# node24-channel.net
KiCad netlist of a schematic drawn in Altium Designer
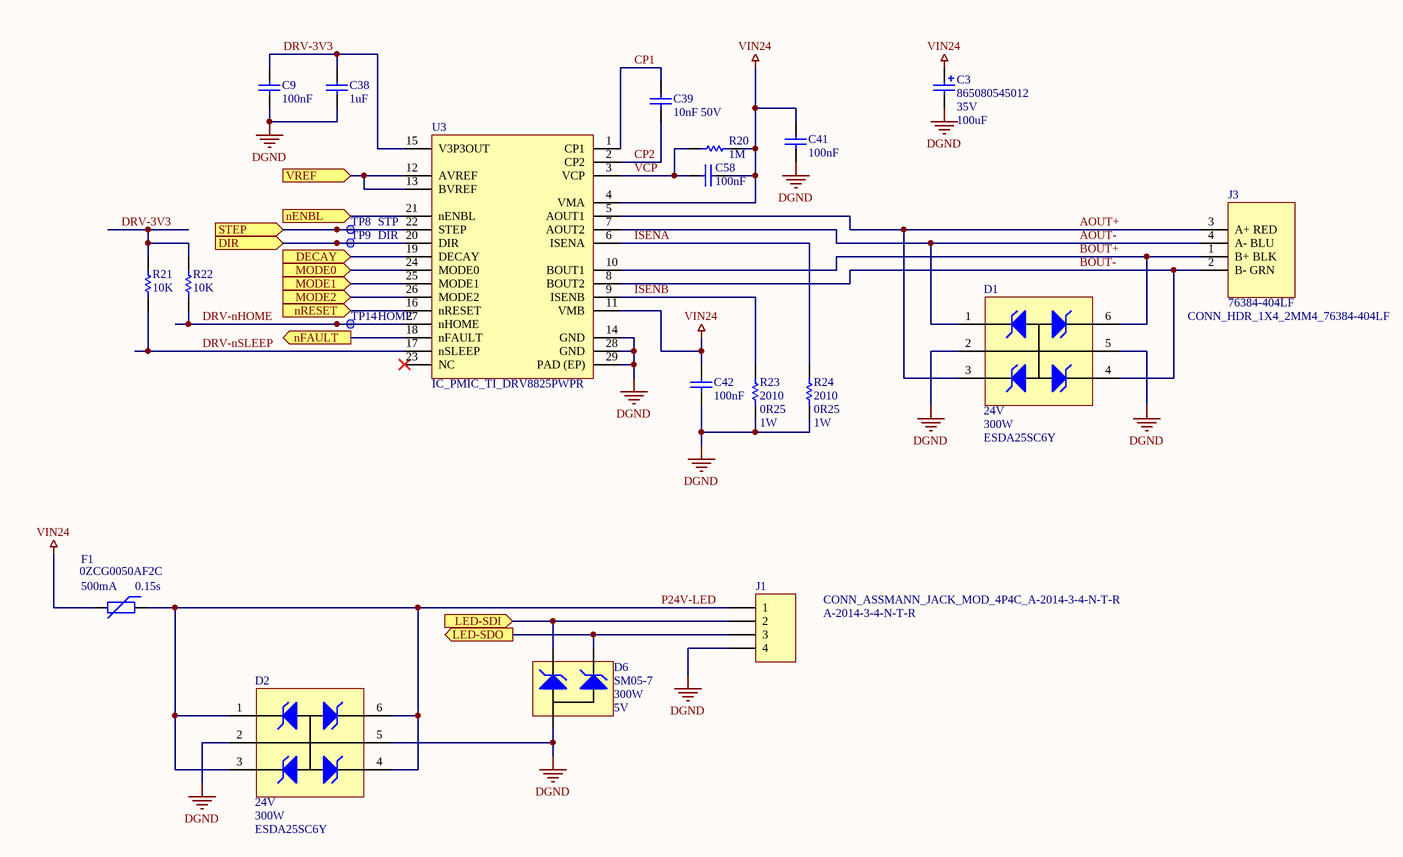
[diagram p0: node24-channel.SchDoc]

(export (version "E")
  (design (tool "Eeschema 10.0.6"))
  (components
    (comp (ref "C3")
      (value "CAP_ALUM_100UF_35V_6MM3_SMT_865080545012")
      (footprint "CAPAE_D6MM3")
      (fields
        (field (name "MANUFACTURER") "Wurth Electronics")
        (field (name "MANUFACTURER PART NUMBER") "865080545012")
        (field (name "VOLTAGE RATING (DC)") "35V")
        (field (name "CAPACITANCE") "100uF")
      )
      (libsource (lib "node") (part "CAP_ALUM_100UF_35V_6MM3_SMT_865080545012"))
    )
    (comp (ref "C9")
      (value "100nF")
      (footprint "CAPC0603(1608)100_L")
      (description "CAP 100nF 50V ±20% 0603 (1608 Metric) Thickness 1mm SMD")
      (fields (field (name "TOLERANCE") "Â±20%"))
      (libsource (lib "Altium Content Vault") (part "CAP"))
    )
    (comp (ref "C38")
      (value "1uF")
      (footprint "CAPC0603(1608)100_L")
      (description "CAP 1uF 10V ±20% 0603 (1608 Metric) Thickness 1mm SMD")
      (fields (field (name "TOLERANCE") "Â±20%"))
      (libsource (lib "Altium Content Vault") (part "CAP"))
    )
    (comp (ref "C39")
      (value "10nF 50V")
      (footprint "CAPC0603(1608)100_L")
      (description "CAP 10nF 50V ±20% 0603 (1608 Metric) Thickness 1mm SMD")
      (fields (field (name "TOLERANCE") "Â±20%"))
      (libsource (lib "Altium Content Vault") (part "CAP"))
    )
    (comp (ref "C41")
      (value "100nF")
      (footprint "CAPC0603(1608)100_L")
      (description "CAP 100nF 50V ±20% 0603 (1608 Metric) Thickness 1mm SMD")
      (fields (field (name "TOLERANCE") "Â±20%"))
      (libsource (lib "Altium Content Vault") (part "CAP"))
    )
    (comp (ref "C42")
      (value "100nF")
      (footprint "CAPC0603(1608)100_L")
      (description "CAP 100nF 50V ±20% 0603 (1608 Metric) Thickness 1mm SMD")
      (fields (field (name "TOLERANCE") "Â±20%"))
      (libsource (lib "Altium Content Vault") (part "CAP"))
    )
    (comp (ref "C58")
      (value "100nF")
      (footprint "CAPC0603(1608)100_L")
      (description "CAP 100nF 50V ±20% 0603 (1608 Metric) Thickness 1mm SMD")
      (fields (field (name "TOLERANCE") "Â±20%"))
      (libsource (lib "Altium Content Vault") (part "CAP"))
    )
    (comp (ref "D1")
      (value "TVS_24V_QUAD_300W_SOT23-6_ESDA25SC6Y")
      (footprint "SOT23-6L")
      (description "TVS DIODE 24VWM 30VC SOT23")
      (fields
        (field (name "MANUFACTURER") "STMicroelectronics")
        (field (name "OPERATING SUPPLY VOLTAGE") "24V")
        (field (name "PEAK PULSE POWER") "300W")
        (field (name "MANUFACTURER PART NUMBER") "ESDA25SC6Y")
      )
      (libsource (lib "node") (part "TVS_24V_QUAD_300W_SOT23-6_ESDA25SC6Y"))
    )
    (comp (ref "D2")
      (value "TVS_24V_QUAD_300W_SOT23-6_ESDA25SC6Y")
      (footprint "SOT23-6L")
      (description "TVS DIODE 24VWM 30VC SOT23")
      (fields
        (field (name "MANUFACTURER") "STMicroelectronics")
        (field (name "OPERATING SUPPLY VOLTAGE") "24V")
        (field (name "PEAK PULSE POWER") "300W")
        (field (name "MANUFACTURER PART NUMBER") "ESDA25SC6Y")
      )
      (libsource (lib "node") (part "TVS_24V_QUAD_300W_SOT23-6_ESDA25SC6Y"))
    )
    (comp (ref "D6")
      (value "TVS_5V_DUAL_SOT23-3_SM05-7")
      (footprint "SOT-23")
      (description "TVS DIODE 5VWM 20.6VC SOT23")
      (fields
        (field (name "MANUFACTURER") "Diodes")
        (field (name "MANUFACTURER PART NUMBER") "SM05-7")
        (field (name "MAX POWER DISSIPATION") "300W")
        (field (name "REVERSE STANDOFF VOLTAGE") "5V")
      )
      (libsource (lib "node") (part "TVS_5V_DUAL_SOT23-3_SM05-7"))
    )
    (comp (ref "F1")
      (value "FUSE_BELFUSE_PTC_30V_500MA_1812_0ZCG0050AF2C")
      (footprint "FUSE_1812")
      (description "PTC RESETTABLE 30V 500MA 1812")
      (fields
        (field (name "MANUFACTURER") "Bel")
        (field (name "HOLD CURRENT") "500mA")
        (field (name "TIME TO TRIP") "0.15s")
        (field (name "MANUFACTURER PART NUMBER") "0ZCG0050AF2C")
      )
      (libsource (lib "node") (part "FUSE_BELFUSE_PTC_30V_500MA_1812_0ZCG0050AF2C"))
    )
    (comp (ref "J1")
      (value "CONN_ASSMANN_JACK_MOD_4P4C_A-2014-3-4-N-T-R")
      (footprint "CON_JACK_MOD_4P4C_ASSMANN_A-2014-3-4-N-T-R")
      (description "CONN MOD JACK 4P4C VERT")
      (fields
        (field (name "MANUFACTURER") "Assmann")
        (field (name "MANUFACTURER PART NUMBER") "A-2014-3-4-N-T-R")
      )
      (libsource (lib "node") (part "CONN_ASSMANN_JACK_MOD_4P4C_A-2014-3-4-N-T-R"))
    )
    (comp (ref "J3")
      (value "CONN_HDR_1X4_2MM4_76384-404LF")
      (footprint "HDR_1x4_2R54_V_M")
      (fields
        (field (name "MANUFACTURER") "Amphenol FCI")
        (field (name "MANUFACTURER PART NUMBER") "76384-404LF")
      )
      (libsource (lib "node") (part "CONN_HDR_1X4_2MM4_76384-404LF"))
    )
    (comp (ref "R20")
      (value "1M")
      (footprint "RESC0603(1608)_L")
      (description "1M 0.1W 1% 0603 (1608 Metric)  SMD")
      (fields (field (name "POWER") "0.1 W") (field (name "TOLERANCE") "1 %"))
      (libsource (lib "Altium Content Vault") (part "RES"))
    )
    (comp (ref "R21")
      (value "10K")
      (footprint "RESC0603(1608)_L")
      (description "10K 0.1W 1% 0603 (1608 Metric)  SMD")
      (fields (field (name "POWER") "0.1 W") (field (name "TOLERANCE") "1 %"))
      (libsource (lib "Altium Content Vault") (part "RES"))
    )
    (comp (ref "R22")
      (value "10K")
      (footprint "RESC0603(1608)_L")
      (description "10K 0.1W 1% 0603 (1608 Metric)  SMD")
      (fields (field (name "POWER") "0.1 W") (field (name "TOLERANCE") "1 %"))
      (libsource (lib "Altium Content Vault") (part "RES"))
    )
    (comp (ref "R23")
      (value "RES_2010_0R25_1W_CSRN2010FKR250")
      (footprint "RES2010N")
      (description "Res Thick Film 2010 0.25 Ohm 1% 1W ±250ppm/C Molded SMD Plastic T/R")
      (fields
        (field (name "MANUFACTURER") "Stackpole Electronics")
        (field (name "MANUFACTURER PART NUMBER") "CSRN2010FKR250")
        (field (name "CASE CODE (IMPERIAL)") "2010")
        (field (name "RESISTANCE") "0R25")
        (field (name "POWER RATING") "1W")
      )
      (libsource (lib "node") (part "RES_2010_0R25_1W_CSRN2010FKR250"))
    )
    (comp (ref "R24")
      (value "RES_2010_0R25_1W_CSRN2010FKR250")
      (footprint "RES2010N")
      (description "Res Thick Film 2010 0.25 Ohm 1% 1W ±250ppm/C Molded SMD Plastic T/R")
      (fields
        (field (name "MANUFACTURER") "Stackpole Electronics")
        (field (name "MANUFACTURER PART NUMBER") "CSRN2010FKR250")
        (field (name "CASE CODE (IMPERIAL)") "2010")
        (field (name "RESISTANCE") "0R25")
        (field (name "POWER RATING") "1W")
      )
      (libsource (lib "node") (part "RES_2010_0R25_1W_CSRN2010FKR250"))
    )
    (comp (ref "TP8")
      (value "STP")
      (footprint "TP_1MM")
      (description "TEST_PAD_NO_PART")
      (fields (field (name "MANUFACTURER PART NUMBER") "None -- copper test pad"))
      (libsource (lib "node") (part "TEST_POINT"))
    )
    (comp (ref "TP9")
      (value "DIR")
      (footprint "TP_1MM")
      (description "TEST_PAD_NO_PART")
      (fields (field (name "MANUFACTURER PART NUMBER") "None -- copper test pad"))
      (libsource (lib "node") (part "TEST_POINT"))
    )
    (comp (ref "TP14")
      (value "HOME")
      (footprint "TP_1MM")
      (description "TEST_PAD_NO_PART")
      (fields (field (name "MANUFACTURER PART NUMBER") "None -- copper test pad"))
      (libsource (lib "node") (part "TEST_POINT"))
    )
    (comp (ref "U3")
      (value "IC_PMIC_TI_DRV8825PWPR")
      (footprint "IC_TSSOP28_0MM65_EP52X31")
      (description "IC MOTOR DRIVER PAR 28HTSSOP")
      (fields
        (field (name "MANUFACTURER") "Texas Instruments")
        (field (name "MANUFACTURER PART NUMBER") "DRV8825PWPR")
      )
      (libsource (lib "node") (part "IC_PMIC_TI_DRV8825PWPR"))
    )
  )
  (nets
    (net (code "1") (name "/AOUT+") (class "Default")
      (node (ref "D1") (pin "3") (pinfunction "K2_3") (pintype "passive"))
      (node (ref "J3") (pin "3") (pinfunction "A+_RED_3") (pintype "passive"))
      (node (ref "U3") (pin "5") (pinfunction "AOUT1_5") (pintype "passive"))
    )
    (net (code "2") (name "/AOUT-") (class "Default")
      (node (ref "D1") (pin "1") (pinfunction "K1_1") (pintype "passive"))
      (node (ref "J3") (pin "4") (pinfunction "A-_BLU_4") (pintype "passive"))
      (node (ref "U3") (pin "7") (pinfunction "AOUT2_7") (pintype "passive"))
    )
    (net (code "3") (name "/BOUT+") (class "Default")
      (node (ref "D1") (pin "6") (pinfunction "K4_6") (pintype "passive"))
      (node (ref "J3") (pin "1") (pinfunction "B+_BLK_1") (pintype "passive"))
      (node (ref "U3") (pin "10") (pinfunction "BOUT1_10") (pintype "passive"))
    )
    (net (code "4") (name "/BOUT-") (class "Default")
      (node (ref "D1") (pin "4") (pinfunction "K3_4") (pintype "passive"))
      (node (ref "J3") (pin "2") (pinfunction "B-_GRN_2") (pintype "passive"))
      (node (ref "U3") (pin "8") (pinfunction "BOUT2_8") (pintype "passive"))
    )
    (net (code "5") (name "/CP1") (class "Default")
      (node (ref "C39") (pin "2") (pinfunction "2_2") (pintype "passive"))
      (node (ref "U3") (pin "1") (pinfunction "CP1_1") (pintype "passive"))
    )
    (net (code "6") (name "/CP2") (class "Default")
      (node (ref "C39") (pin "1") (pinfunction "1_1") (pintype "passive"))
      (node (ref "U3") (pin "2") (pinfunction "CP2_2") (pintype "passive"))
    )
    (net (code "7") (name "/DECAY") (class "Default")
      (node (ref "U3") (pin "19") (pinfunction "DECAY_19") (pintype "passive"))
    )
    (net (code "8") (name "/DIR") (class "Default")
      (node (ref "TP9") (pin "1") (pinfunction "1_1") (pintype "passive"))
      (node (ref "U3") (pin "20") (pinfunction "DIR_20") (pintype "passive"))
    )
    (net (code "9") (name "/DRV-3V3") (class "Default")
      (node (ref "C38") (pin "2") (pinfunction "2_2") (pintype "passive"))
      (node (ref "C9") (pin "2") (pinfunction "2_2") (pintype "passive"))
      (node (ref "R21") (pin "2") (pinfunction "2_2") (pintype "passive"))
      (node (ref "R22") (pin "2") (pinfunction "2_2") (pintype "passive"))
      (node (ref "U3") (pin "15") (pinfunction "V3P3OUT_15") (pintype "passive"))
    )
    (net (code "10") (name "/DRV-nHOME") (class "Default")
      (node (ref "R22") (pin "1") (pinfunction "1_1") (pintype "passive"))
      (node (ref "TP14") (pin "1") (pinfunction "1_1") (pintype "passive"))
      (node (ref "U3") (pin "27") (pinfunction "nHOME_27") (pintype "passive"))
    )
    (net (code "11") (name "/DRV-nSLEEP") (class "Default")
      (node (ref "R21") (pin "1") (pinfunction "1_1") (pintype "passive"))
      (node (ref "U3") (pin "17") (pinfunction "nSLEEP_17") (pintype "passive"))
    )
    (net (code "12") (name "/ISENA") (class "Default")
      (node (ref "R24") (pin "1") (pinfunction "1_1") (pintype "passive"))
      (node (ref "U3") (pin "6") (pinfunction "ISENA_6") (pintype "passive"))
    )
    (net (code "13") (name "/ISENB") (class "Default")
      (node (ref "R23") (pin "1") (pinfunction "1_1") (pintype "passive"))
      (node (ref "U3") (pin "9") (pinfunction "ISENB_9") (pintype "passive"))
    )
    (net (code "14") (name "/LED-SDI") (class "Default")
      (node (ref "D6") (pin "1") (pinfunction "K1_1") (pintype "passive"))
      (node (ref "J1") (pin "2") (pinfunction "2_2") (pintype "passive"))
    )
    (net (code "15") (name "/LED-SDO") (class "Default")
      (node (ref "D6") (pin "2") (pinfunction "K2_2") (pintype "passive"))
      (node (ref "J1") (pin "3") (pinfunction "3_3") (pintype "passive"))
    )
    (net (code "16") (name "/MODE0") (class "Default")
      (node (ref "U3") (pin "24") (pinfunction "MODE0_24") (pintype "passive"))
    )
    (net (code "17") (name "/MODE1") (class "Default")
      (node (ref "U3") (pin "25") (pinfunction "MODE1_25") (pintype "passive"))
    )
    (net (code "18") (name "/MODE2") (class "Default")
      (node (ref "U3") (pin "26") (pinfunction "MODE2_26") (pintype "passive"))
    )
    (net (code "19") (name "/P24V-LED") (class "Default")
      (node (ref "D2") (pin "1") (pinfunction "K1_1") (pintype "passive"))
      (node (ref "D2") (pin "3") (pinfunction "K2_3") (pintype "passive"))
      (node (ref "D2") (pin "4") (pinfunction "K3_4") (pintype "passive"))
      (node (ref "D2") (pin "6") (pinfunction "K4_6") (pintype "passive"))
      (node (ref "F1") (pin "1") (pinfunction "1_1") (pintype "passive"))
      (node (ref "J1") (pin "1") (pinfunction "1_1") (pintype "passive"))
    )
    (net (code "20") (name "/STEP") (class "Default")
      (node (ref "TP8") (pin "1") (pinfunction "1_1") (pintype "passive"))
      (node (ref "U3") (pin "22") (pinfunction "STEP_22") (pintype "passive"))
    )
    (net (code "21") (name "/VCP") (class "Default")
      (node (ref "C58") (pin "2") (pinfunction "2_2") (pintype "passive"))
      (node (ref "R20") (pin "1") (pinfunction "1_1") (pintype "passive"))
      (node (ref "U3") (pin "3") (pinfunction "VCP_3") (pintype "passive"))
    )
    (net (code "22") (name "/VREF") (class "Default")
      (node (ref "U3") (pin "12") (pinfunction "AVREF_12") (pintype "passive"))
      (node (ref "U3") (pin "13") (pinfunction "BVREF_13") (pintype "passive"))
    )
    (net (code "23") (name "/nENBL") (class "Default")
      (node (ref "U3") (pin "21") (pinfunction "nENBL_21") (pintype "passive"))
    )
    (net (code "24") (name "/nFAULT") (class "Default")
      (node (ref "U3") (pin "18") (pinfunction "nFAULT_18") (pintype "passive"))
    )
    (net (code "25") (name "/nRESET") (class "Default")
      (node (ref "U3") (pin "16") (pinfunction "nRESET_16") (pintype "passive"))
    )
    (net (code "26") (name "DGND") (class "Default")
      (node (ref "C3") (pin "2") (pinfunction "2_2") (pintype "passive"))
      (node (ref "C38") (pin "1") (pinfunction "1_1") (pintype "passive"))
      (node (ref "C41") (pin "2") (pinfunction "2_2") (pintype "passive"))
      (node (ref "C42") (pin "2") (pinfunction "2_2") (pintype "passive"))
      (node (ref "C9") (pin "1") (pinfunction "1_1") (pintype "passive"))
      (node (ref "D1") (pin "2") (pinfunction "A1_2") (pintype "passive"))
      (node (ref "D1") (pin "5") (pinfunction "A2_5") (pintype "passive"))
      (node (ref "D2") (pin "2") (pinfunction "A1_2") (pintype "passive"))
      (node (ref "D2") (pin "5") (pinfunction "A2_5") (pintype "passive"))
      (node (ref "D6") (pin "3") (pinfunction "A_3") (pintype "passive"))
      (node (ref "J1") (pin "4") (pinfunction "4_4") (pintype "passive"))
      (node (ref "R23") (pin "2") (pinfunction "2_2") (pintype "passive"))
      (node (ref "R24") (pin "2") (pinfunction "2_2") (pintype "passive"))
      (node (ref "U3") (pin "14") (pinfunction "GND_14") (pintype "passive"))
      (node (ref "U3") (pin "28") (pinfunction "GND_28") (pintype "passive"))
      (node (ref "U3") (pin "29") (pinfunction "PAD_(EP)_29") (pintype "passive"))
    )
    (net (code "27") (name "VIN24") (class "Default")
      (node (ref "C3") (pin "1") (pinfunction "1_1") (pintype "passive"))
      (node (ref "C41") (pin "1") (pinfunction "1_1") (pintype "passive"))
      (node (ref "C42") (pin "1") (pinfunction "1_1") (pintype "passive"))
      (node (ref "C58") (pin "1") (pinfunction "1_1") (pintype "passive"))
      (node (ref "F1") (pin "2") (pinfunction "2_2") (pintype "passive"))
      (node (ref "R20") (pin "2") (pinfunction "2_2") (pintype "passive"))
      (node (ref "U3") (pin "11") (pinfunction "VMB_11") (pintype "passive"))
      (node (ref "U3") (pin "4") (pinfunction "VMA_4") (pintype "passive"))
    )
    (net (code "28") (name "unconnected-(U3-NC-Pad23)") (class "Default")
      (node (ref "U3") (pin "23") (pinfunction "NC_23") (pintype "passive+no_connect"))
    )
  )
)
